# S3220A1.net
KiCad netlist of a schematic drawn in Altium Designer
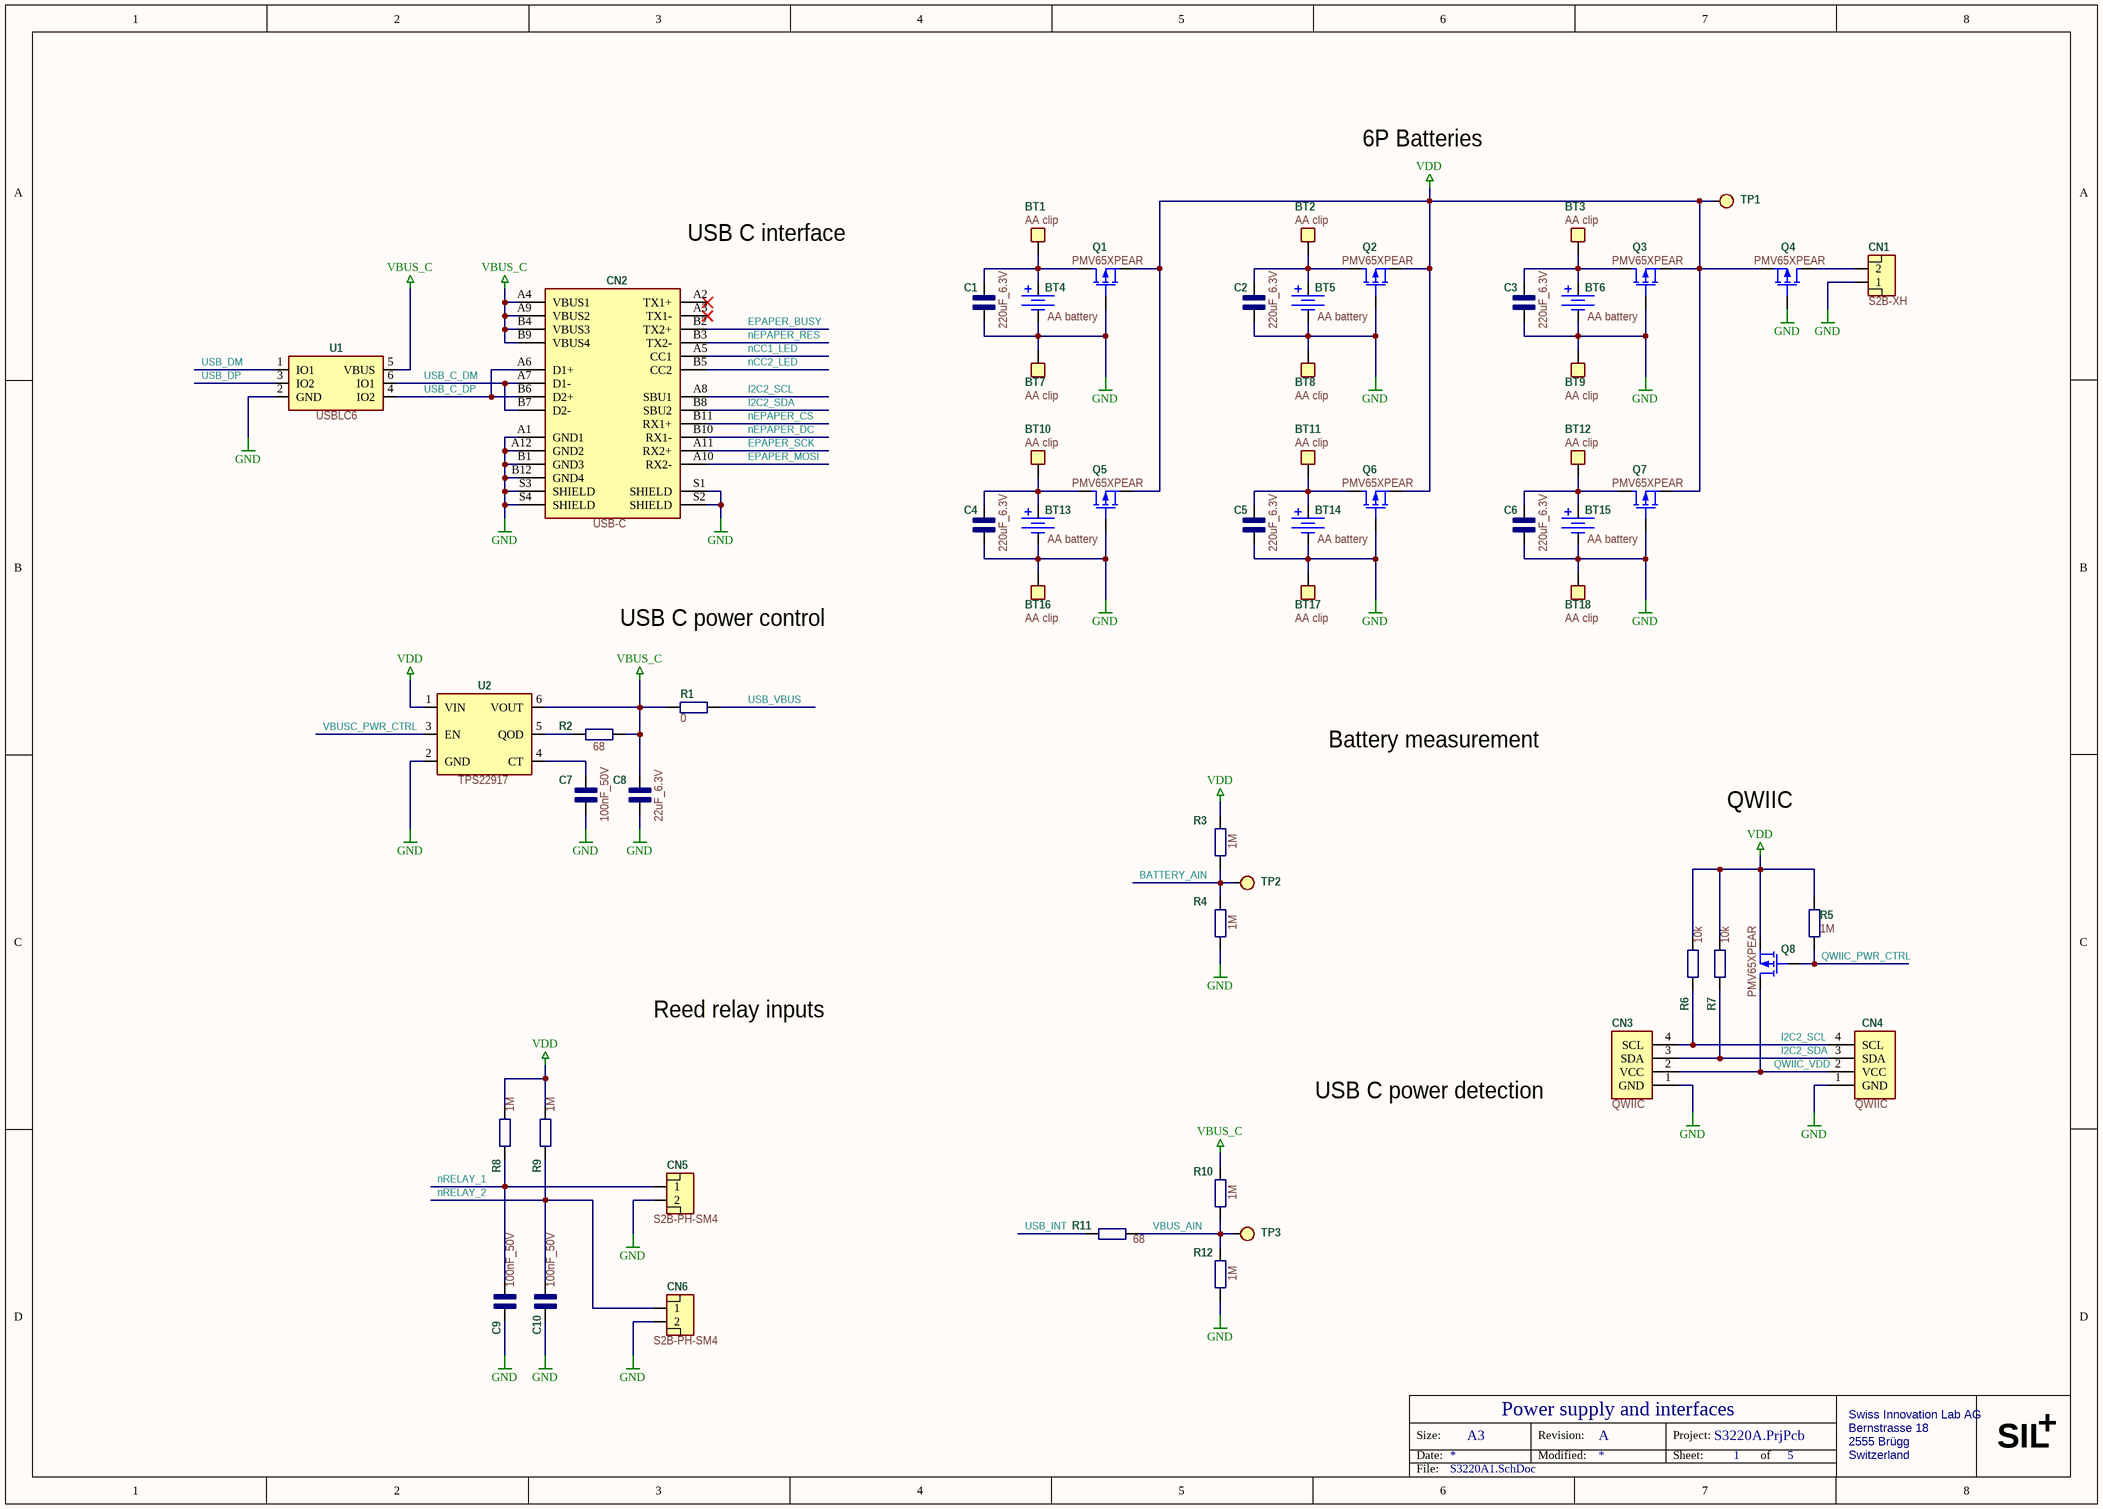
[diagram p0: S3220A1.SchDoc]

(export (version "E")
  (design (tool "Eeschema 10.0.6"))
  (components
    (comp (ref "BT1")
      (value "AA clip")
      (footprint "BT_AA-TH-CLIP")
      (description "Battery Contact Clip A, AA 1 Cell PC Pin")
      (fields
        (field (name "MANUFACTURER") "Keystone Electronics")
        (field (name "MANUFACTURER PART NUMBER") "92")
      )
      (libsource (lib "") (part "BT_AA-TH-CLIP_1"))
    )
    (comp (ref "BT2")
      (value "AA clip")
      (footprint "BT_AA-TH-CLIP")
      (description "Battery Contact Clip A, AA 1 Cell PC Pin")
      (fields
        (field (name "MANUFACTURER") "Keystone Electronics")
        (field (name "MANUFACTURER PART NUMBER") "92")
      )
      (libsource (lib "") (part "BT_AA-TH-CLIP_1"))
    )
    (comp (ref "BT3")
      (value "AA clip")
      (footprint "BT_AA-TH-CLIP")
      (description "Battery Contact Clip A, AA 1 Cell PC Pin")
      (fields
        (field (name "MANUFACTURER") "Keystone Electronics")
        (field (name "MANUFACTURER PART NUMBER") "92")
      )
      (libsource (lib "") (part "BT_AA-TH-CLIP_1"))
    )
    (comp (ref "BT4")
      (value "AA battery")
      (footprint "BT_AA-battery")
      (fields (field (name "MANUFACTURER") "SIL"))
      (libsource (lib "SIL") (part "BT_AA-battery"))
    )
    (comp (ref "BT5")
      (value "AA battery")
      (footprint "BT_AA-battery")
      (fields (field (name "MANUFACTURER") "SIL"))
      (libsource (lib "SIL") (part "BT_AA-battery"))
    )
    (comp (ref "BT6")
      (value "AA battery")
      (footprint "BT_AA-battery")
      (fields (field (name "MANUFACTURER") "SIL"))
      (libsource (lib "SIL") (part "BT_AA-battery"))
    )
    (comp (ref "BT7")
      (value "AA clip")
      (footprint "BT_AA-TH-CLIP")
      (description "Battery Contact Clip A, AA 1 Cell PC Pin")
      (fields
        (field (name "MANUFACTURER") "Keystone Electronics")
        (field (name "MANUFACTURER PART NUMBER") "92")
      )
      (libsource (lib "SIL") (part "BT_AA-TH-CLIP"))
    )
    (comp (ref "BT8")
      (value "AA clip")
      (footprint "BT_AA-TH-CLIP")
      (description "Battery Contact Clip A, AA 1 Cell PC Pin")
      (fields
        (field (name "MANUFACTURER") "Keystone Electronics")
        (field (name "MANUFACTURER PART NUMBER") "92")
      )
      (libsource (lib "SIL") (part "BT_AA-TH-CLIP"))
    )
    (comp (ref "BT9")
      (value "AA clip")
      (footprint "BT_AA-TH-CLIP")
      (description "Battery Contact Clip A, AA 1 Cell PC Pin")
      (fields
        (field (name "MANUFACTURER") "Keystone Electronics")
        (field (name "MANUFACTURER PART NUMBER") "92")
      )
      (libsource (lib "SIL") (part "BT_AA-TH-CLIP"))
    )
    (comp (ref "BT10")
      (value "AA clip")
      (footprint "BT_AA-TH-CLIP")
      (description "Battery Contact Clip A, AA 1 Cell PC Pin")
      (fields
        (field (name "MANUFACTURER") "Keystone Electronics")
        (field (name "MANUFACTURER PART NUMBER") "92")
      )
      (libsource (lib "") (part "BT_AA-TH-CLIP_1"))
    )
    (comp (ref "BT11")
      (value "AA clip")
      (footprint "BT_AA-TH-CLIP")
      (description "Battery Contact Clip A, AA 1 Cell PC Pin")
      (fields
        (field (name "MANUFACTURER") "Keystone Electronics")
        (field (name "MANUFACTURER PART NUMBER") "92")
      )
      (libsource (lib "") (part "BT_AA-TH-CLIP_1"))
    )
    (comp (ref "BT12")
      (value "AA clip")
      (footprint "BT_AA-TH-CLIP")
      (description "Battery Contact Clip A, AA 1 Cell PC Pin")
      (fields
        (field (name "MANUFACTURER") "Keystone Electronics")
        (field (name "MANUFACTURER PART NUMBER") "92")
      )
      (libsource (lib "") (part "BT_AA-TH-CLIP_1"))
    )
    (comp (ref "BT13")
      (value "AA battery")
      (footprint "BT_AA-battery")
      (fields (field (name "MANUFACTURER") "SIL"))
      (libsource (lib "SIL") (part "BT_AA-battery"))
    )
    (comp (ref "BT14")
      (value "AA battery")
      (footprint "BT_AA-battery")
      (fields (field (name "MANUFACTURER") "SIL"))
      (libsource (lib "SIL") (part "BT_AA-battery"))
    )
    (comp (ref "BT15")
      (value "AA battery")
      (footprint "BT_AA-battery")
      (fields (field (name "MANUFACTURER") "SIL"))
      (libsource (lib "SIL") (part "BT_AA-battery"))
    )
    (comp (ref "BT16")
      (value "AA clip")
      (footprint "BT_AA-TH-CLIP")
      (description "Battery Contact Clip A, AA 1 Cell PC Pin")
      (fields
        (field (name "MANUFACTURER") "Keystone Electronics")
        (field (name "MANUFACTURER PART NUMBER") "92")
      )
      (libsource (lib "SIL") (part "BT_AA-TH-CLIP"))
    )
    (comp (ref "BT17")
      (value "AA clip")
      (footprint "BT_AA-TH-CLIP")
      (description "Battery Contact Clip A, AA 1 Cell PC Pin")
      (fields
        (field (name "MANUFACTURER") "Keystone Electronics")
        (field (name "MANUFACTURER PART NUMBER") "92")
      )
      (libsource (lib "SIL") (part "BT_AA-TH-CLIP"))
    )
    (comp (ref "BT18")
      (value "AA clip")
      (footprint "BT_AA-TH-CLIP")
      (description "Battery Contact Clip A, AA 1 Cell PC Pin")
      (fields
        (field (name "MANUFACTURER") "Keystone Electronics")
        (field (name "MANUFACTURER PART NUMBER") "92")
      )
      (libsource (lib "SIL") (part "BT_AA-TH-CLIP"))
    )
    (comp (ref "C1")
      (value "220uF_6.3V")
      (footprint "C_1206")
      (description "220µF ±20% 6.3V Ceramic Capacitor X5R 1206 (3216 Metric)")
      (fields
        (field (name "MANUFACTURER") "Murata Electronics North America")
        (field (name "MANUFACTURER PART NUMBER") "GRM31CR60J227ME11L")
      )
      (libsource (lib "SIL") (part "C_220uF_6.3V"))
    )
    (comp (ref "C2")
      (value "220uF_6.3V")
      (footprint "C_1206")
      (description "220µF ±20% 6.3V Ceramic Capacitor X5R 1206 (3216 Metric)")
      (fields
        (field (name "MANUFACTURER") "Murata Electronics North America")
        (field (name "MANUFACTURER PART NUMBER") "GRM31CR60J227ME11L")
      )
      (libsource (lib "SIL") (part "C_220uF_6.3V"))
    )
    (comp (ref "C3")
      (value "220uF_6.3V")
      (footprint "C_1206")
      (description "220µF ±20% 6.3V Ceramic Capacitor X5R 1206 (3216 Metric)")
      (fields
        (field (name "MANUFACTURER") "Murata Electronics North America")
        (field (name "MANUFACTURER PART NUMBER") "GRM31CR60J227ME11L")
      )
      (libsource (lib "SIL") (part "C_220uF_6.3V"))
    )
    (comp (ref "C4")
      (value "220uF_6.3V")
      (footprint "C_1206")
      (description "220µF ±20% 6.3V Ceramic Capacitor X5R 1206 (3216 Metric)")
      (fields
        (field (name "MANUFACTURER") "Murata Electronics North America")
        (field (name "MANUFACTURER PART NUMBER") "GRM31CR60J227ME11L")
      )
      (libsource (lib "SIL") (part "C_220uF_6.3V"))
    )
    (comp (ref "C5")
      (value "220uF_6.3V")
      (footprint "C_1206")
      (description "220µF ±20% 6.3V Ceramic Capacitor X5R 1206 (3216 Metric)")
      (fields
        (field (name "MANUFACTURER") "Murata Electronics North America")
        (field (name "MANUFACTURER PART NUMBER") "GRM31CR60J227ME11L")
      )
      (libsource (lib "SIL") (part "C_220uF_6.3V"))
    )
    (comp (ref "C6")
      (value "220uF_6.3V")
      (footprint "C_1206")
      (description "220µF ±20% 6.3V Ceramic Capacitor X5R 1206 (3216 Metric)")
      (fields
        (field (name "MANUFACTURER") "Murata Electronics North America")
        (field (name "MANUFACTURER PART NUMBER") "GRM31CR60J227ME11L")
      )
      (libsource (lib "SIL") (part "C_220uF_6.3V"))
    )
    (comp (ref "C7")
      (value "100nF_50V")
      (footprint "SIL:C_0603")
      (description "0.1µF ±10% 50V Ceramic Capacitor X7R 0603 (1608 Metric)")
      (fields
        (field (name "MANUFACTURER") "TDK")
        (field (name "MANUFACTURER PART NUMBER") "C1608X7R1H104K080AA")
      )
      (libsource (lib "SIL") (part "C_100nF_50V"))
    )
    (comp (ref "C8")
      (value "22uF_6.3V")
      (footprint "SIL:C_0603")
      (description "22µF ±20% 6.3V Ceramic Capacitor X5R 0603 (1608 Metric)")
      (fields
        (field (name "MANUFACTURER") "Samsung Electro-Mechanics")
        (field (name "MANUFACTURER PART NUMBER") "CL10A226MQ8NRNC")
      )
      (libsource (lib "SIL") (part "C_22uF_6V3"))
    )
    (comp (ref "C9")
      (value "100nF_50V")
      (footprint "SIL:C_0603")
      (description "0.1µF ±10% 50V Ceramic Capacitor X7R 0603 (1608 Metric)")
      (fields
        (field (name "MANUFACTURER") "TDK")
        (field (name "MANUFACTURER PART NUMBER") "C1608X7R1H104K080AA")
      )
      (libsource (lib "SIL") (part "C_100nF_50V"))
    )
    (comp (ref "C10")
      (value "100nF_50V")
      (footprint "SIL:C_0603")
      (description "0.1µF ±10% 50V Ceramic Capacitor X7R 0603 (1608 Metric)")
      (fields
        (field (name "MANUFACTURER") "TDK")
        (field (name "MANUFACTURER PART NUMBER") "C1608X7R1H104K080AA")
      )
      (libsource (lib "SIL") (part "C_100nF_50V"))
    )
    (comp (ref "CN1")
      (value "S2B-XH")
      (footprint "CN_S2B-XH-A")
      (description "Connector Header Through Hole, Right Angle 2 position 0.098\" (2.50mm)")
      (fields
        (field (name "MANUFACTURER") "JST Sales America Inc.")
        (field (name "MANUFACTURER PART NUMBER") "S2B-XH-A(LF)(SN)")
      )
      (libsource (lib "SIL") (part "CN_S2B-XH"))
    )
    (comp (ref "CN2")
      (value "USB-C")
      (footprint "CN_USB-C-RA_2")
      (fields
        (field (name "MANUFACTURER") "CUI Devices")
        (field (name "MANUFACTURER PART NUMBER") "UJ31-CH-G-SMT-TR-67")
      )
      (libsource (lib "SIL") (part "CN_USB-C-RA_2"))
    )
    (comp (ref "CN3")
      (value "QWIIC")
      (footprint "CN_SM04B-SRSS-TB")
      (description "Connector Header Surface Mount, Right Angle 4 position 0.039\" (1.00mm)")
      (fields
        (field (name "MANUFACTURER") "JST Sales America Inc.")
        (field (name "MANUFACTURER PART NUMBER") "SM04B-SRSS-TB(LF)(SN)")
      )
      (libsource (lib "SIL") (part "CN_QWICC"))
    )
    (comp (ref "CN4")
      (value "QWIIC")
      (footprint "CN_SM04B-SRSS-TB")
      (description "Connector Header Surface Mount, Right Angle 4 position 0.039\" (1.00mm)")
      (fields
        (field (name "MANUFACTURER") "JST Sales America Inc.")
        (field (name "MANUFACTURER PART NUMBER") "SM04B-SRSS-TB(LF)(SN)")
      )
      (libsource (lib "") (part "CN_QWICC_1"))
    )
    (comp (ref "CN5")
      (value "S2B-PH-SM4")
      (footprint "CN_S2B-PH-SM4")
      (description "Connector Header Surface Mount, Right Angle 2 position 0.079\" (2.00mm)")
      (fields
        (field (name "MANUFACTURER") "JST Sales America Inc.")
        (field (name "MANUFACTURER PART NUMBER") "S2B-PH-SM4-TB(LF)(SN)")
      )
      (libsource (lib "SIL") (part "CN_S2B-PH-SM4"))
    )
    (comp (ref "CN6")
      (value "S2B-PH-SM4")
      (footprint "CN_S2B-PH-SM4")
      (description "Connector Header Surface Mount, Right Angle 2 position 0.079\" (2.00mm)")
      (fields
        (field (name "MANUFACTURER") "JST Sales America Inc.")
        (field (name "MANUFACTURER PART NUMBER") "S2B-PH-SM4-TB(LF)(SN)")
      )
      (libsource (lib "SIL") (part "CN_S2B-PH-SM4"))
    )
    (comp (ref "Q1")
      (value "PMV65XPEAR")
      (footprint "U_SOT23-3")
      (description "P-Channel 20V 2.8A (Ta) 480mW (Ta), 6.25W (Tc) Surface Mount TO-236AB (SOT23)")
      (fields (field (name "MANUFACTURER") "Nexperia USA Inc."))
      (libsource (lib "SIL") (part "Q_PMV65"))
    )
    (comp (ref "Q2")
      (value "PMV65XPEAR")
      (footprint "U_SOT23-3")
      (description "P-Channel 20V 2.8A (Ta) 480mW (Ta), 6.25W (Tc) Surface Mount TO-236AB (SOT23)")
      (fields (field (name "MANUFACTURER") "Nexperia USA Inc."))
      (libsource (lib "SIL") (part "Q_PMV65"))
    )
    (comp (ref "Q3")
      (value "PMV65XPEAR")
      (footprint "U_SOT23-3")
      (description "P-Channel 20V 2.8A (Ta) 480mW (Ta), 6.25W (Tc) Surface Mount TO-236AB (SOT23)")
      (fields (field (name "MANUFACTURER") "Nexperia USA Inc."))
      (libsource (lib "SIL") (part "Q_PMV65"))
    )
    (comp (ref "Q4")
      (value "PMV65XPEAR")
      (footprint "U_SOT23-3")
      (description "P-Channel 20V 2.8A (Ta) 480mW (Ta), 6.25W (Tc) Surface Mount TO-236AB (SOT23)")
      (fields (field (name "MANUFACTURER") "Nexperia USA Inc."))
      (libsource (lib "SIL") (part "Q_PMV65"))
    )
    (comp (ref "Q5")
      (value "PMV65XPEAR")
      (footprint "U_SOT23-3")
      (description "P-Channel 20V 2.8A (Ta) 480mW (Ta), 6.25W (Tc) Surface Mount TO-236AB (SOT23)")
      (fields (field (name "MANUFACTURER") "Nexperia USA Inc."))
      (libsource (lib "SIL") (part "Q_PMV65"))
    )
    (comp (ref "Q6")
      (value "PMV65XPEAR")
      (footprint "U_SOT23-3")
      (description "P-Channel 20V 2.8A (Ta) 480mW (Ta), 6.25W (Tc) Surface Mount TO-236AB (SOT23)")
      (fields (field (name "MANUFACTURER") "Nexperia USA Inc."))
      (libsource (lib "SIL") (part "Q_PMV65"))
    )
    (comp (ref "Q7")
      (value "PMV65XPEAR")
      (footprint "U_SOT23-3")
      (description "P-Channel 20V 2.8A (Ta) 480mW (Ta), 6.25W (Tc) Surface Mount TO-236AB (SOT23)")
      (fields (field (name "MANUFACTURER") "Nexperia USA Inc."))
      (libsource (lib "SIL") (part "Q_PMV65"))
    )
    (comp (ref "Q8")
      (value "PMV65XPEAR")
      (footprint "U_SOT23-3")
      (description "P-Channel 20V 2.8A (Ta) 480mW (Ta), 6.25W (Tc) Surface Mount TO-236AB (SOT23)")
      (fields (field (name "MANUFACTURER") "Nexperia USA Inc."))
      (libsource (lib "SIL") (part "Q_PMV65"))
    )
    (comp (ref "R1")
      (value "0")
      (footprint "SIL:R_0603")
      (description "0 Ohms Jumper 0.1W, 1/10W Chip Resistor 0603 (1608 Metric) Automotive AEC-Q200 Thick Film")
      (fields
        (field (name "MANUFACTURER") "Panasonic Electronic Components")
        (field (name "MANUFACTURER PART NUMBER") "ERJ-3GEY0R00V")
      )
      (libsource (lib "SIL") (part "R_0_1%"))
    )
    (comp (ref "R2")
      (value "68")
      (footprint "SIL:R_0603")
      (description "68 Ohms ±1% 0.1W, 1/10W Chip Resistor 0603 (1608 Metric) Automotive AEC-Q200 Thick Film")
      (fields
        (field (name "MANUFACTURER") "Panasonic Electronic Components")
        (field (name "MANUFACTURER PART NUMBER") "ERJ-3EKF68R0V")
      )
      (libsource (lib "") (part "R_68_1%_1"))
    )
    (comp (ref "R3")
      (value "1M")
      (footprint "SIL:R_0603")
      (description "1 MOhms ±1% 0.1W, 1/10W Chip Resistor 0603 (1608 Metric) Automotive AEC-Q200 Thick Film")
      (fields
        (field (name "MANUFACTURER") "Panasonic Electronic Components")
        (field (name "MANUFACTURER PART NUMBER") "ERJ-3EKF1004V")
      )
      (libsource (lib "") (part "R_1M_1%_1"))
    )
    (comp (ref "R4")
      (value "1M")
      (footprint "SIL:R_0603")
      (description "1 MOhms ±1% 0.1W, 1/10W Chip Resistor 0603 (1608 Metric) Automotive AEC-Q200 Thick Film")
      (fields
        (field (name "MANUFACTURER") "Panasonic Electronic Components")
        (field (name "MANUFACTURER PART NUMBER") "ERJ-3EKF1004V")
      )
      (libsource (lib "") (part "R_1M_1%_1"))
    )
    (comp (ref "R5")
      (value "1M")
      (footprint "SIL:R_0603")
      (description "1 MOhms ±1% 0.1W, 1/10W Chip Resistor 0603 (1608 Metric) Automotive AEC-Q200 Thick Film")
      (fields
        (field (name "MANUFACTURER") "Panasonic Electronic Components")
        (field (name "MANUFACTURER PART NUMBER") "ERJ-3EKF1004V")
      )
      (libsource (lib "SIL") (part "R_1M_1%"))
    )
    (comp (ref "R6")
      (value "10k")
      (footprint "SIL:R_0603")
      (description "10 kOhms ±1% 0.1W, 1/10W Chip Resistor 0603 (1608 Metric) Automotive AEC-Q200 Thick Film")
      (fields
        (field (name "MANUFACTURER") "Panasonic Electronic Components")
        (field (name "MANUFACTURER PART NUMBER") "ERJ-3EKF1002V")
      )
      (libsource (lib "SIL") (part "R_10k_1%"))
    )
    (comp (ref "R7")
      (value "10k")
      (footprint "SIL:R_0603")
      (description "10 kOhms ±1% 0.1W, 1/10W Chip Resistor 0603 (1608 Metric) Automotive AEC-Q200 Thick Film")
      (fields
        (field (name "MANUFACTURER") "Panasonic Electronic Components")
        (field (name "MANUFACTURER PART NUMBER") "ERJ-3EKF1002V")
      )
      (libsource (lib "SIL") (part "R_10k_1%"))
    )
    (comp (ref "R8")
      (value "1M")
      (footprint "SIL:R_0603")
      (description "1 MOhms ±1% 0.1W, 1/10W Chip Resistor 0603 (1608 Metric) Automotive AEC-Q200 Thick Film")
      (fields
        (field (name "MANUFACTURER") "Panasonic Electronic Components")
        (field (name "MANUFACTURER PART NUMBER") "ERJ-3EKF1004V")
      )
      (libsource (lib "") (part "R_1M_1%_1"))
    )
    (comp (ref "R9")
      (value "1M")
      (footprint "SIL:R_0603")
      (description "1 MOhms ±1% 0.1W, 1/10W Chip Resistor 0603 (1608 Metric) Automotive AEC-Q200 Thick Film")
      (fields
        (field (name "MANUFACTURER") "Panasonic Electronic Components")
        (field (name "MANUFACTURER PART NUMBER") "ERJ-3EKF1004V")
      )
      (libsource (lib "") (part "R_1M_1%_1"))
    )
    (comp (ref "R10")
      (value "1M")
      (footprint "SIL:R_0603")
      (description "1 MOhms ±1% 0.1W, 1/10W Chip Resistor 0603 (1608 Metric) Automotive AEC-Q200 Thick Film")
      (fields
        (field (name "MANUFACTURER") "Panasonic Electronic Components")
        (field (name "MANUFACTURER PART NUMBER") "ERJ-3EKF1004V")
      )
      (libsource (lib "") (part "R_1M_1%_1"))
    )
    (comp (ref "R11")
      (value "68")
      (footprint "SIL:R_0603")
      (description "68 Ohms ±1% 0.1W, 1/10W Chip Resistor 0603 (1608 Metric) Automotive AEC-Q200 Thick Film")
      (fields
        (field (name "MANUFACTURER") "Panasonic Electronic Components")
        (field (name "MANUFACTURER PART NUMBER") "ERJ-3EKF68R0V")
      )
      (libsource (lib "SIL") (part "R_68_1%"))
    )
    (comp (ref "R12")
      (value "1M")
      (footprint "SIL:R_0603")
      (description "1 MOhms ±1% 0.1W, 1/10W Chip Resistor 0603 (1608 Metric) Automotive AEC-Q200 Thick Film")
      (fields
        (field (name "MANUFACTURER") "Panasonic Electronic Components")
        (field (name "MANUFACTURER PART NUMBER") "ERJ-3EKF1004V")
      )
      (libsource (lib "") (part "R_1M_1%_1"))
    )
    (comp (ref "TP1")
      (value "Test point")
      (footprint "SIL:TP_SMD_R1.0mm")
      (fields (field (name "MANUFACTURER") "Swiss Innovation Lab"))
      (libsource (lib "SIL") (part "TP_Test_point"))
    )
    (comp (ref "TP2")
      (value "Test point")
      (footprint "SIL:TP_SMD_R1.0mm")
      (fields (field (name "MANUFACTURER") "Swiss Innovation Lab"))
      (libsource (lib "SIL") (part "TP_Test_point"))
    )
    (comp (ref "TP3")
      (value "Test point")
      (footprint "SIL:TP_SMD_R1.0mm")
      (fields (field (name "MANUFACTURER") "Swiss Innovation Lab"))
      (libsource (lib "SIL") (part "TP_Test_point"))
    )
    (comp (ref "U1")
      (value "USBLC6")
      (footprint "U_SOT23-6")
      (description "TVS DIODE 5.25V 17V SOT23-6")
      (fields
        (field (name "MANUFACTURER") "STMicroelectronics")
        (field (name "MANUFACTURER PART NUMBER") "USBLC6-2SC6Y")
      )
      (libsource (lib "SIL") (part "U_USBLC6"))
    )
    (comp (ref "U2")
      (value "TPS22917")
      (footprint "U_SOT23-6")
      (description "Power Switch/Driver 1:1 P-Channel 2A SOT-23-6")
      (fields
        (field (name "MANUFACTURER") "Texas Instruments")
        (field (name "MANUFACTURER PART NUMBER") "TPS22917DBVR")
      )
      (libsource (lib "SIL") (part "U_TPS22917"))
    )
  )
  (nets
    (net (code "1") (name "/BATTERY_AIN") (class "Default")
      (node (ref "R3") (pin "1") (pinfunction "1_1") (pintype "passive"))
      (node (ref "R4") (pin "2") (pinfunction "2_2") (pintype "passive"))
      (node (ref "TP2") (pin "1") (pinfunction "1_1") (pintype "passive"))
    )
    (net (code "2") (name "/EPAPER_BUSY") (class "Default")
      (node (ref "CN2") (pin "B2") (pinfunction "TX2+_B2") (pintype "passive"))
    )
    (net (code "3") (name "/EPAPER_MOSI") (class "Default")
      (node (ref "CN2") (pin "A10") (pinfunction "RX2-_A10") (pintype "passive"))
    )
    (net (code "4") (name "/EPAPER_SCK") (class "Default")
      (node (ref "CN2") (pin "A11") (pinfunction "RX2+_A11") (pintype "passive"))
    )
    (net (code "5") (name "/I2C2_SCL") (class "Default")
      (node (ref "CN2") (pin "A8") (pinfunction "SBU1_A8") (pintype "passive"))
      (node (ref "CN3") (pin "4") (pinfunction "SCL_4") (pintype "passive"))
      (node (ref "CN4") (pin "4") (pinfunction "SCL_4") (pintype "passive"))
      (node (ref "R6") (pin "1") (pinfunction "1_1") (pintype "passive"))
    )
    (net (code "6") (name "/I2C2_SDA") (class "Default")
      (node (ref "CN2") (pin "B8") (pinfunction "SBU2_B8") (pintype "passive"))
      (node (ref "CN3") (pin "3") (pinfunction "SDA_3") (pintype "passive"))
      (node (ref "CN4") (pin "3") (pinfunction "SDA_3") (pintype "passive"))
      (node (ref "R7") (pin "1") (pinfunction "1_1") (pintype "passive"))
    )
    (net (code "7") (name "/QWIIC_PWR_CTRL") (class "Default")
      (node (ref "Q8") (pin "1") (pinfunction "G_1") (pintype "passive"))
      (node (ref "R5") (pin "1") (pinfunction "1_1") (pintype "passive"))
    )
    (net (code "8") (name "/QWIIC_VDD") (class "Default")
      (node (ref "CN3") (pin "2") (pinfunction "VCC_2") (pintype "passive"))
      (node (ref "CN4") (pin "2") (pinfunction "VCC_2") (pintype "passive"))
      (node (ref "Q8") (pin "3") (pinfunction "D_3") (pintype "passive"))
    )
    (net (code "9") (name "/USB_C_DM") (class "Default")
      (node (ref "CN2") (pin "A7") (pinfunction "D1-_A7") (pintype "passive"))
      (node (ref "CN2") (pin "B7") (pinfunction "D2-_B7") (pintype "passive"))
      (node (ref "U1") (pin "6") (pinfunction "IO1_6") (pintype "passive"))
    )
    (net (code "10") (name "/USB_C_DP") (class "Default")
      (node (ref "CN2") (pin "A6") (pinfunction "D1+_A6") (pintype "passive"))
      (node (ref "CN2") (pin "B6") (pinfunction "D2+_B6") (pintype "passive"))
      (node (ref "U1") (pin "4") (pinfunction "IO2_4") (pintype "passive"))
    )
    (net (code "11") (name "/USB_DM") (class "Default")
      (node (ref "U1") (pin "1") (pinfunction "IO1_1") (pintype "passive"))
    )
    (net (code "12") (name "/USB_DP") (class "Default")
      (node (ref "U1") (pin "3") (pinfunction "IO2_3") (pintype "passive"))
    )
    (net (code "13") (name "/USB_INT") (class "Default")
      (node (ref "R11") (pin "1") (pinfunction "1_1") (pintype "passive"))
    )
    (net (code "14") (name "/USB_VBUS") (class "Default")
      (node (ref "R1") (pin "2") (pinfunction "2_2") (pintype "passive"))
    )
    (net (code "15") (name "/VBUSC_PWR_CTRL") (class "Default")
      (node (ref "U2") (pin "3") (pinfunction "EN_3") (pintype "passive"))
    )
    (net (code "16") (name "/VBUS_AIN") (class "Default")
      (node (ref "R10") (pin "1") (pinfunction "1_1") (pintype "passive"))
      (node (ref "R11") (pin "2") (pinfunction "2_2") (pintype "passive"))
      (node (ref "R12") (pin "2") (pinfunction "2_2") (pintype "passive"))
      (node (ref "TP3") (pin "1") (pinfunction "1_1") (pintype "passive"))
    )
    (net (code "17") (name "/nCC1_LED") (class "Default")
      (node (ref "CN2") (pin "A5") (pinfunction "CC1_A5") (pintype "passive"))
    )
    (net (code "18") (name "/nCC2_LED") (class "Default")
      (node (ref "CN2") (pin "B5") (pinfunction "CC2_B5") (pintype "passive"))
    )
    (net (code "19") (name "/nEPAPER_CS") (class "Default")
      (node (ref "CN2") (pin "B11") (pinfunction "RX1+_B11") (pintype "passive"))
    )
    (net (code "20") (name "/nEPAPER_DC") (class "Default")
      (node (ref "CN2") (pin "B10") (pinfunction "RX1-_B10") (pintype "passive"))
    )
    (net (code "21") (name "/nEPAPER_RES") (class "Default")
      (node (ref "CN2") (pin "B3") (pinfunction "TX2-_B3") (pintype "passive"))
    )
    (net (code "22") (name "/nRELAY_1") (class "Default")
      (node (ref "C9") (pin "2") (pintype "passive"))
      (node (ref "CN5") (pin "1") (pinfunction "1_1") (pintype "passive"))
      (node (ref "R8") (pin "1") (pinfunction "1_1") (pintype "passive"))
    )
    (net (code "23") (name "/nRELAY_2") (class "Default")
      (node (ref "C10") (pin "2") (pintype "passive"))
      (node (ref "CN6") (pin "1") (pinfunction "1_1") (pintype "passive"))
      (node (ref "R9") (pin "1") (pinfunction "1_1") (pintype "passive"))
    )
    (net (code "24") (name "GND") (class "Default")
      (node (ref "BT16") (pin "1") (pinfunction "1_1") (pintype "passive"))
      (node (ref "BT17") (pin "1") (pinfunction "1_1") (pintype "passive"))
      (node (ref "BT18") (pin "1") (pinfunction "1_1") (pintype "passive"))
      (node (ref "BT7") (pin "1") (pinfunction "1_1") (pintype "passive"))
      (node (ref "BT8") (pin "1") (pinfunction "1_1") (pintype "passive"))
      (node (ref "BT9") (pin "1") (pinfunction "1_1") (pintype "passive"))
      (node (ref "C1") (pin "1") (pintype "passive"))
      (node (ref "C10") (pin "1") (pintype "passive"))
      (node (ref "C2") (pin "1") (pintype "passive"))
      (node (ref "C3") (pin "1") (pintype "passive"))
      (node (ref "C4") (pin "1") (pintype "passive"))
      (node (ref "C5") (pin "1") (pintype "passive"))
      (node (ref "C6") (pin "1") (pintype "passive"))
      (node (ref "C7") (pin "1") (pintype "passive"))
      (node (ref "C8") (pin "1") (pintype "passive"))
      (node (ref "C9") (pin "1") (pintype "passive"))
      (node (ref "CN1") (pin "1") (pinfunction "1_1") (pintype "passive"))
      (node (ref "CN2") (pin "A1") (pinfunction "GND1_A1") (pintype "power_in"))
      (node (ref "CN2") (pin "A12") (pinfunction "GND2_A12") (pintype "power_in"))
      (node (ref "CN2") (pin "B1") (pinfunction "GND3_B1") (pintype "power_in"))
      (node (ref "CN2") (pin "B12") (pinfunction "GND4_B12") (pintype "power_in"))
      (node (ref "CN2") (pin "S1") (pinfunction "SHIELD_S1") (pintype "power_in"))
      (node (ref "CN2") (pin "S2") (pinfunction "SHIELD_S2") (pintype "power_in"))
      (node (ref "CN2") (pin "S3") (pinfunction "SHIELD_S3") (pintype "power_in"))
      (node (ref "CN2") (pin "S4") (pinfunction "SHIELD_S4") (pintype "power_in"))
      (node (ref "CN3") (pin "1") (pinfunction "GND_1") (pintype "passive"))
      (node (ref "CN4") (pin "1") (pinfunction "GND_1") (pintype "passive"))
      (node (ref "CN5") (pin "2") (pinfunction "2_2") (pintype "passive"))
      (node (ref "CN6") (pin "2") (pinfunction "2_2") (pintype "passive"))
      (node (ref "Q1") (pin "1") (pinfunction "G_1") (pintype "passive"))
      (node (ref "Q2") (pin "1") (pinfunction "G_1") (pintype "passive"))
      (node (ref "Q3") (pin "1") (pinfunction "G_1") (pintype "passive"))
      (node (ref "Q4") (pin "1") (pinfunction "G_1") (pintype "passive"))
      (node (ref "Q5") (pin "1") (pinfunction "G_1") (pintype "passive"))
      (node (ref "Q6") (pin "1") (pinfunction "G_1") (pintype "passive"))
      (node (ref "Q7") (pin "1") (pinfunction "G_1") (pintype "passive"))
      (node (ref "R12") (pin "1") (pinfunction "1_1") (pintype "passive"))
      (node (ref "R4") (pin "1") (pinfunction "1_1") (pintype "passive"))
      (node (ref "U1") (pin "2") (pinfunction "GND_2") (pintype "power_in"))
      (node (ref "U2") (pin "2") (pinfunction "GND_2") (pintype "power_in"))
    )
    (net (code "25") (name "Net-(Q1-D)") (class "Default")
      (node (ref "BT1") (pin "1") (pinfunction "1_1") (pintype "passive"))
      (node (ref "C1") (pin "2") (pintype "passive"))
      (node (ref "Q1") (pin "3") (pinfunction "D_3") (pintype "passive"))
    )
    (net (code "26") (name "Net-(Q2-D)") (class "Default")
      (node (ref "BT2") (pin "1") (pinfunction "1_1") (pintype "passive"))
      (node (ref "C2") (pin "2") (pintype "passive"))
      (node (ref "Q2") (pin "3") (pinfunction "D_3") (pintype "passive"))
    )
    (net (code "27") (name "Net-(Q3-D)") (class "Default")
      (node (ref "BT3") (pin "1") (pinfunction "1_1") (pintype "passive"))
      (node (ref "C3") (pin "2") (pintype "passive"))
      (node (ref "Q3") (pin "3") (pinfunction "D_3") (pintype "passive"))
    )
    (net (code "28") (name "Net-(Q4-D)") (class "Default")
      (node (ref "CN1") (pin "2") (pinfunction "2_2") (pintype "passive"))
      (node (ref "Q4") (pin "3") (pinfunction "D_3") (pintype "passive"))
    )
    (net (code "29") (name "Net-(Q5-D)") (class "Default")
      (node (ref "BT10") (pin "1") (pinfunction "1_1") (pintype "passive"))
      (node (ref "C4") (pin "2") (pintype "passive"))
      (node (ref "Q5") (pin "3") (pinfunction "D_3") (pintype "passive"))
    )
    (net (code "30") (name "Net-(Q6-D)") (class "Default")
      (node (ref "BT11") (pin "1") (pinfunction "1_1") (pintype "passive"))
      (node (ref "C5") (pin "2") (pintype "passive"))
      (node (ref "Q6") (pin "3") (pinfunction "D_3") (pintype "passive"))
    )
    (net (code "31") (name "Net-(Q7-D)") (class "Default")
      (node (ref "BT12") (pin "1") (pinfunction "1_1") (pintype "passive"))
      (node (ref "C6") (pin "2") (pintype "passive"))
      (node (ref "Q7") (pin "3") (pinfunction "D_3") (pintype "passive"))
    )
    (net (code "32") (name "Net-(U2-CT)") (class "Default")
      (node (ref "C7") (pin "2") (pintype "passive"))
      (node (ref "U2") (pin "4") (pinfunction "CT_4") (pintype "passive"))
    )
    (net (code "33") (name "Net-(U2-QOD)") (class "Default")
      (node (ref "R2") (pin "2") (pinfunction "2_2") (pintype "passive"))
      (node (ref "U2") (pin "5") (pinfunction "QOD_5") (pintype "passive"))
    )
    (net (code "34") (name "VBUS_C") (class "Default")
      (node (ref "C8") (pin "2") (pintype "passive"))
      (node (ref "CN2") (pin "A4") (pinfunction "VBUS1_A4") (pintype "power_in"))
      (node (ref "CN2") (pin "A9") (pinfunction "VBUS2_A9") (pintype "power_in"))
      (node (ref "CN2") (pin "B4") (pinfunction "VBUS3_B4") (pintype "power_in"))
      (node (ref "CN2") (pin "B9") (pinfunction "VBUS4_B9") (pintype "power_in"))
      (node (ref "R1") (pin "1") (pinfunction "1_1") (pintype "passive"))
      (node (ref "R10") (pin "2") (pinfunction "2_2") (pintype "passive"))
      (node (ref "R2") (pin "1") (pinfunction "1_1") (pintype "passive"))
      (node (ref "U1") (pin "5") (pinfunction "VBUS_5") (pintype "power_in"))
      (node (ref "U2") (pin "6") (pinfunction "VOUT_6") (pintype "passive"))
    )
    (net (code "35") (name "VDD") (class "Default")
      (node (ref "Q1") (pin "2") (pinfunction "S_2") (pintype "passive"))
      (node (ref "Q2") (pin "2") (pinfunction "S_2") (pintype "passive"))
      (node (ref "Q3") (pin "2") (pinfunction "S_2") (pintype "passive"))
      (node (ref "Q4") (pin "2") (pinfunction "S_2") (pintype "passive"))
      (node (ref "Q5") (pin "2") (pinfunction "S_2") (pintype "passive"))
      (node (ref "Q6") (pin "2") (pinfunction "S_2") (pintype "passive"))
      (node (ref "Q7") (pin "2") (pinfunction "S_2") (pintype "passive"))
      (node (ref "Q8") (pin "2") (pinfunction "S_2") (pintype "passive"))
      (node (ref "R3") (pin "2") (pinfunction "2_2") (pintype "passive"))
      (node (ref "R5") (pin "2") (pinfunction "2_2") (pintype "passive"))
      (node (ref "R6") (pin "2") (pinfunction "2_2") (pintype "passive"))
      (node (ref "R7") (pin "2") (pinfunction "2_2") (pintype "passive"))
      (node (ref "R8") (pin "2") (pinfunction "2_2") (pintype "passive"))
      (node (ref "R9") (pin "2") (pinfunction "2_2") (pintype "passive"))
      (node (ref "TP1") (pin "1") (pinfunction "1_1") (pintype "passive"))
      (node (ref "U2") (pin "1") (pinfunction "VIN_1") (pintype "power_in"))
    )
    (net (code "36") (name "unconnected-(CN2-TX1+-PadA2)") (class "Default")
      (node (ref "CN2") (pin "A2") (pinfunction "TX1+_A2") (pintype "passive+no_connect"))
    )
    (net (code "37") (name "unconnected-(CN2-TX1--PadA3)") (class "Default")
      (node (ref "CN2") (pin "A3") (pinfunction "TX1-_A3") (pintype "passive+no_connect"))
    )
  )
)
